# BSPD_TNN_V1_0.net
KiCad netlist of a schematic drawn in EAGLE
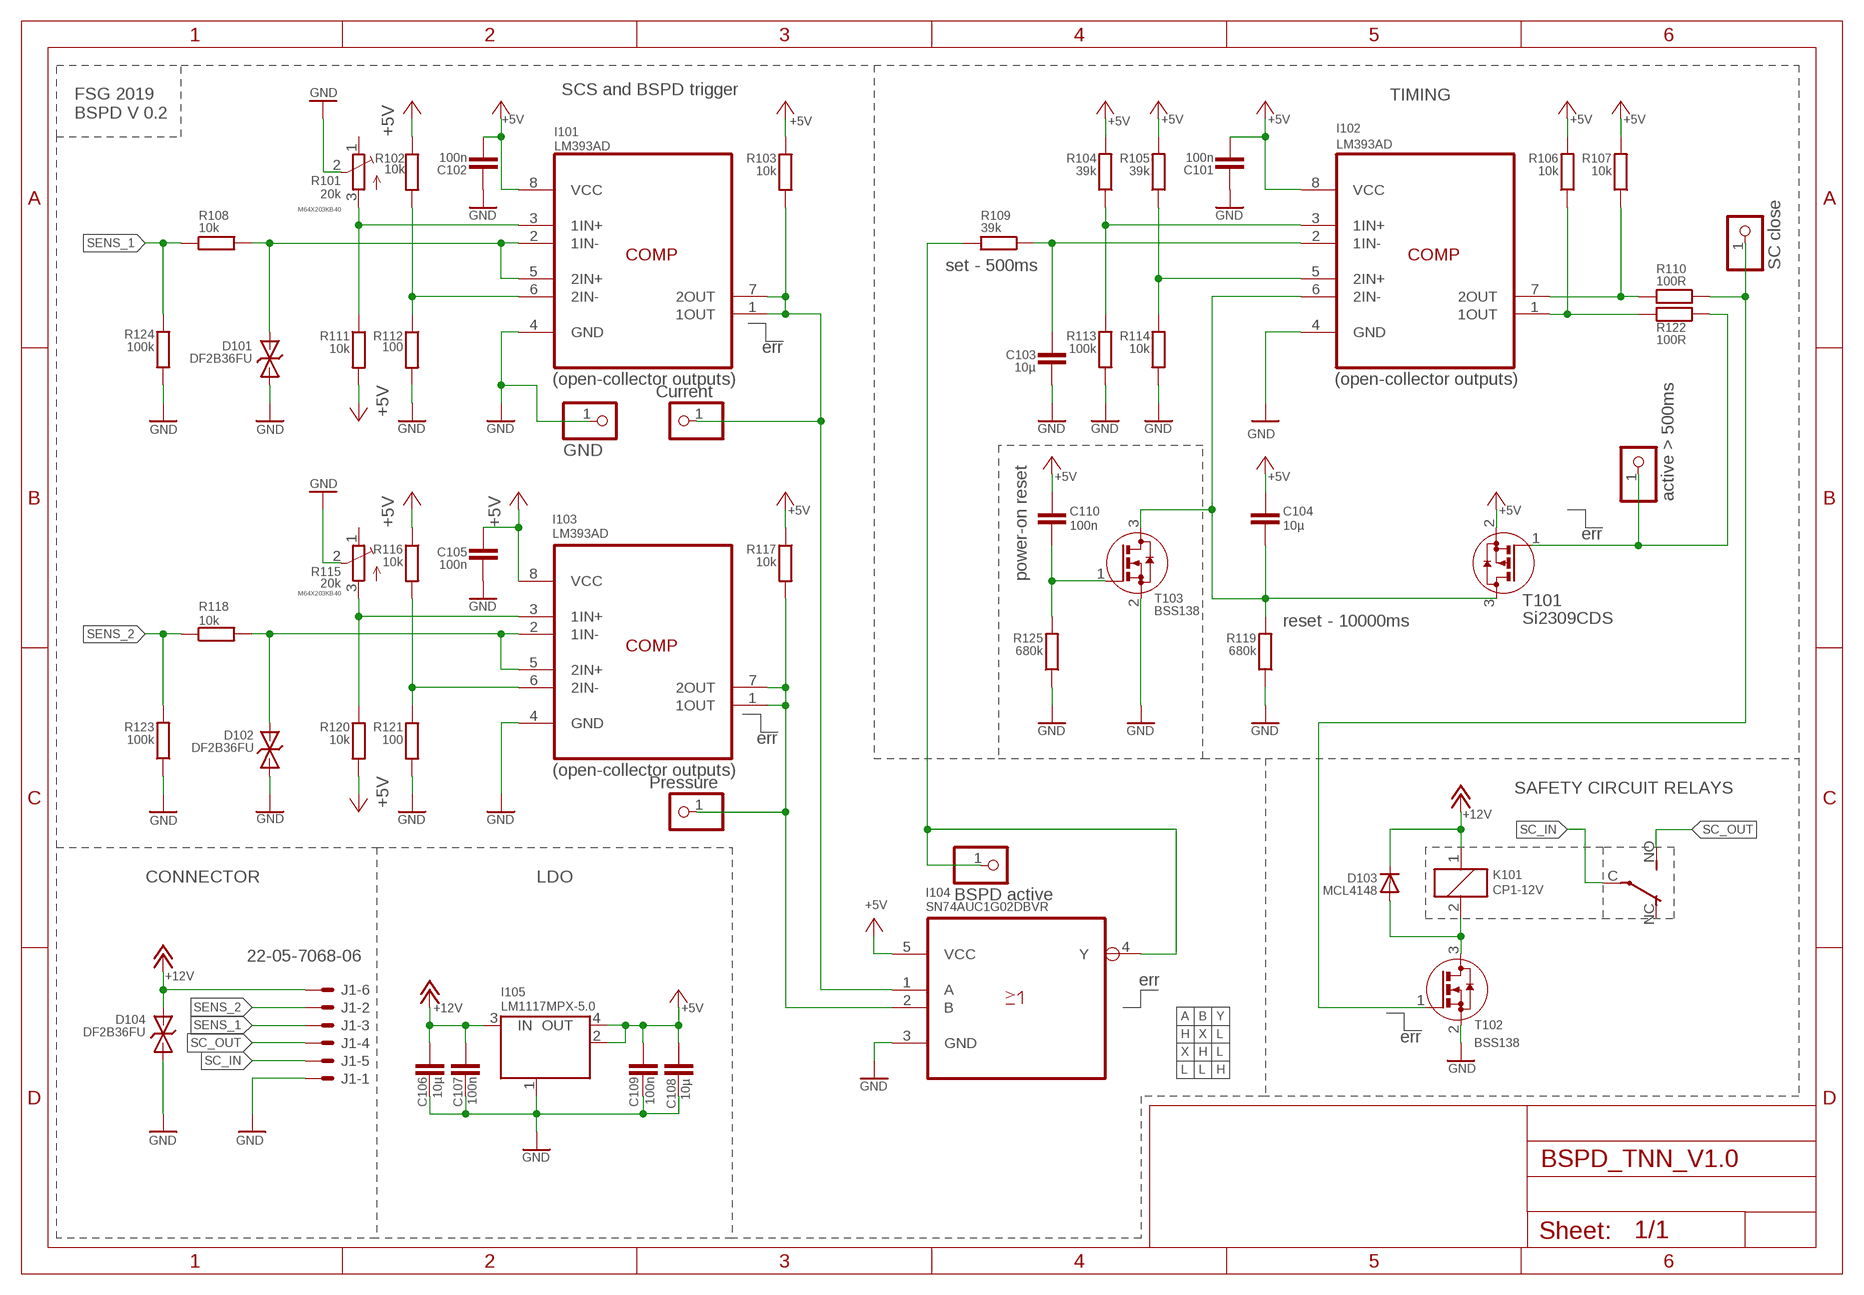
[diagram p0: schematic, sheet 1]

(export (version "E")
  (design (tool "Eeschema 10.0.6"))
  (components
    (comp (ref "C101")
      (value "100n")
      (footprint "eagle-import:C0603")
      (libsource (lib "eagle-import") (part "resistor_C-EUC0603"))
    )
    (comp (ref "C102")
      (value "100n")
      (footprint "eagle-import:C0603")
      (libsource (lib "eagle-import") (part "resistor_C-EUC0603"))
    )
    (comp (ref "C103")
      (value "10µ")
      (footprint "eagle-import:C1206")
      (libsource (lib "eagle-import") (part "C-EUC1206"))
    )
    (comp (ref "C104")
      (value "10µ")
      (footprint "eagle-import:C1206K")
      (libsource (lib "eagle-import") (part "C-EUC1206K"))
    )
    (comp (ref "C105")
      (value "100n")
      (footprint "eagle-import:C0603")
      (libsource (lib "eagle-import") (part "resistor_C-EUC0603"))
    )
    (comp (ref "C106")
      (value "10µ")
      (footprint "eagle-import:C1206")
      (libsource (lib "eagle-import") (part "C-EUC1206"))
    )
    (comp (ref "C107")
      (value "100n")
      (footprint "eagle-import:C0603")
      (libsource (lib "eagle-import") (part "C-EUC0603"))
    )
    (comp (ref "C108")
      (value "10µ")
      (footprint "eagle-import:C1206")
      (libsource (lib "eagle-import") (part "C-EUC1206"))
    )
    (comp (ref "C109")
      (value "100n")
      (footprint "eagle-import:C0603")
      (libsource (lib "eagle-import") (part "C-EUC0603"))
    )
    (comp (ref "C110")
      (value "100n")
      (footprint "eagle-import:C0603")
      (libsource (lib "eagle-import") (part "C-EUC0603"))
    )
    (comp (ref "D101")
      (value "DF2B36FU")
      (footprint "eagle-import:SOD323")
      (libsource (lib "eagle-import") (part "DF2B36FU"))
    )
    (comp (ref "D102")
      (value "DF2B36FU")
      (footprint "eagle-import:SOD323")
      (libsource (lib "eagle-import") (part "DF2B36FU"))
    )
    (comp (ref "D103")
      (value "MCL4148")
      (footprint "eagle-import:MICROMELF")
      (libsource (lib "eagle-import") (part "D.MCL4148"))
    )
    (comp (ref "D104")
      (value "DF2B36FU")
      (footprint "eagle-import:SOD323")
      (libsource (lib "eagle-import") (part "DF2B36FU"))
    )
    (comp (ref "I101")
      (value "LM393AD")
      (footprint "eagle-import:SOIC127P600X175-8N")
      (libsource (lib "eagle-import") (part "LM393AD"))
    )
    (comp (ref "I102")
      (value "LM393AD")
      (footprint "eagle-import:SOIC127P600X175-8N")
      (libsource (lib "eagle-import") (part "LM393AD"))
    )
    (comp (ref "I103")
      (value "LM393AD")
      (footprint "eagle-import:SOIC127P600X175-8N")
      (libsource (lib "eagle-import") (part "LM393AD"))
    )
    (comp (ref "I104")
      (value "SN74AUC1G02DBVR")
      (footprint "eagle-import:SOT95P280X145-5N")
      (fields (field (name "MPN") "NC7SZ08M5X"))
      (libsource (lib "eagle-import") (part "NC7SZ08M5X"))
    )
    (comp (ref "I105")
      (value "LM1117MPX-5.0")
      (footprint "eagle-import:LINEAR_SOT223")
      (fields (field (name "PART_NUMBER") "LM1117IMPX-5.0"))
      (libsource (lib "eagle-import") (part "0022_LM1117IMPX-5.0"))
    )
    (comp (ref "J1")
      (value "22-05-7068-06")
      (footprint "eagle-import:7395-06")
      (fields (field (name "MF") "MOLEX"))
      (libsource (lib "eagle-import") (part "22-?-0605-7068"))
    )
    (comp (ref "JP1")
      (value "Pressure")
      (footprint "eagle-import:1X01")
      (libsource (lib "eagle-import") (part "PINHD-1X1"))
    )
    (comp (ref "JP2")
      (value "Current")
      (footprint "eagle-import:1X01")
      (libsource (lib "eagle-import") (part "PINHD-1X1"))
    )
    (comp (ref "JP3")
      (value "BSPD active")
      (footprint "eagle-import:1X01")
      (libsource (lib "eagle-import") (part "PINHD-1X1"))
    )
    (comp (ref "JP4")
      (value "active > 500ms")
      (footprint "eagle-import:1X01")
      (libsource (lib "eagle-import") (part "PINHD-1X1"))
    )
    (comp (ref "JP5")
      (value "SC close")
      (footprint "eagle-import:1X01")
      (libsource (lib "eagle-import") (part "PINHD-1X1"))
    )
    (comp (ref "JP6")
      (value "GND")
      (footprint "eagle-import:1X01")
      (libsource (lib "eagle-import") (part "PINHD-1X1"))
    )
    (comp (ref "K101")
      (value "CP1-12V")
      (footprint "eagle-import:CP1")
      (fields (field (name "MF") "AROMAT/ MATSUSHITA"))
      (libsource (lib "eagle-import") (part "CP1?-12V"))
    )
    (comp (ref "R101")
      (value "20k")
      (footprint "eagle-import:M64X201KB40")
      (libsource (lib "eagle-import") (part "POTI.M64X201KB40"))
    )
    (comp (ref "R102")
      (value "10k")
      (footprint "eagle-import:R0603")
      (libsource (lib "eagle-import") (part "R-EU_R0603"))
    )
    (comp (ref "R103")
      (value "10k")
      (footprint "eagle-import:R0603")
      (libsource (lib "eagle-import") (part "R-EU_R0603"))
    )
    (comp (ref "R104")
      (value "39k")
      (footprint "eagle-import:R0603")
      (libsource (lib "eagle-import") (part "R-EU_R0603"))
    )
    (comp (ref "R105")
      (value "39k")
      (footprint "eagle-import:R0603")
      (libsource (lib "eagle-import") (part "R-EU_R0603"))
    )
    (comp (ref "R106")
      (value "10k")
      (footprint "eagle-import:R0603")
      (libsource (lib "eagle-import") (part "R-EU_R0603"))
    )
    (comp (ref "R107")
      (value "10k")
      (footprint "eagle-import:R0603")
      (libsource (lib "eagle-import") (part "R-EU_R0603"))
    )
    (comp (ref "R108")
      (value "10k")
      (footprint "eagle-import:R0603")
      (libsource (lib "eagle-import") (part "R-EU_R0603"))
    )
    (comp (ref "R109")
      (value "39k")
      (footprint "eagle-import:R0603")
      (libsource (lib "eagle-import") (part "R-EU_R0603"))
    )
    (comp (ref "R110")
      (value "100R")
      (footprint "eagle-import:R0603")
      (libsource (lib "eagle-import") (part "R-EU_R0603"))
    )
    (comp (ref "R111")
      (value "10k")
      (footprint "eagle-import:R0603")
      (libsource (lib "eagle-import") (part "R-EU_R0603"))
    )
    (comp (ref "R112")
      (value "100")
      (footprint "eagle-import:R0603")
      (libsource (lib "eagle-import") (part "R-EU_R0603"))
    )
    (comp (ref "R113")
      (value "100k")
      (footprint "eagle-import:R0603")
      (libsource (lib "eagle-import") (part "R-EU_R0603"))
    )
    (comp (ref "R114")
      (value "10k")
      (footprint "eagle-import:R0603")
      (libsource (lib "eagle-import") (part "R-EU_R0603"))
    )
    (comp (ref "R115")
      (value "20k")
      (footprint "eagle-import:M64X201KB40")
      (libsource (lib "eagle-import") (part "POTI.M64X201KB40"))
    )
    (comp (ref "R116")
      (value "10k")
      (footprint "eagle-import:R0603")
      (libsource (lib "eagle-import") (part "R-EU_R0603"))
    )
    (comp (ref "R117")
      (value "10k")
      (footprint "eagle-import:R0603")
      (libsource (lib "eagle-import") (part "R-EU_R0603"))
    )
    (comp (ref "R118")
      (value "10k")
      (footprint "eagle-import:R0603")
      (libsource (lib "eagle-import") (part "R-EU_R0603"))
    )
    (comp (ref "R119")
      (value "680k")
      (footprint "eagle-import:R0603")
      (libsource (lib "eagle-import") (part "R-EU_R0603"))
    )
    (comp (ref "R120")
      (value "10k")
      (footprint "eagle-import:R0603")
      (libsource (lib "eagle-import") (part "R-EU_R0603"))
    )
    (comp (ref "R121")
      (value "100")
      (footprint "eagle-import:R0603")
      (libsource (lib "eagle-import") (part "R-EU_R0603"))
    )
    (comp (ref "R122")
      (value "100R")
      (footprint "eagle-import:R0603")
      (libsource (lib "eagle-import") (part "R-EU_R0603"))
    )
    (comp (ref "R123")
      (value "100k")
      (footprint "eagle-import:R0603")
      (libsource (lib "eagle-import") (part "R-EU_R0603"))
    )
    (comp (ref "R124")
      (value "100k")
      (footprint "eagle-import:R0603")
      (libsource (lib "eagle-import") (part "R-EU_R0603"))
    )
    (comp (ref "R125")
      (value "680k")
      (footprint "eagle-import:R0603")
      (libsource (lib "eagle-import") (part "R-EU_R0603"))
    )
    (comp (ref "T101")
      (value "Si2309CDS")
      (footprint "eagle-import:SOT-23")
      (libsource (lib "eagle-import") (part "P-MOSFET.SOT23"))
    )
    (comp (ref "T102")
      (value "BSS138")
      (footprint "eagle-import:SOT-23")
      (libsource (lib "eagle-import") (part "N-MOSFET.SOT23"))
    )
    (comp (ref "T103")
      (value "BSS138")
      (footprint "eagle-import:SOT-23")
      (libsource (lib "eagle-import") (part "N-MOSFET.SOT23"))
    )
  )
  (nets
    (net (code "1") (name "+5V") (class "Default")
      (node (ref "C101") (pin "2") (pinfunction "2_2") (pintype "passive"))
      (node (ref "C102") (pin "2") (pinfunction "2_2") (pintype "passive"))
      (node (ref "C104") (pin "1") (pinfunction "1_1") (pintype "passive"))
      (node (ref "C105") (pin "2") (pinfunction "2_2") (pintype "passive"))
      (node (ref "C108") (pin "1") (pinfunction "1_1") (pintype "passive"))
      (node (ref "C109") (pin "2") (pinfunction "2_2") (pintype "passive"))
      (node (ref "C110") (pin "1") (pinfunction "1_1") (pintype "passive"))
      (node (ref "I101") (pin "8") (pinfunction "VCC_8") (pintype "power_in"))
      (node (ref "I102") (pin "8") (pinfunction "VCC_8") (pintype "power_in"))
      (node (ref "I103") (pin "8") (pinfunction "VCC_8") (pintype "power_in"))
      (node (ref "I104") (pin "5") (pinfunction "VCC_5") (pintype "power_in"))
      (node (ref "I105") (pin "2") (pinfunction "OUT_2") (pintype "passive"))
      (node (ref "I105") (pin "4") (pinfunction "OUT_4") (pintype "passive"))
      (node (ref "R102") (pin "1") (pinfunction "1_1") (pintype "passive"))
      (node (ref "R103") (pin "1") (pinfunction "1_1") (pintype "passive"))
      (node (ref "R104") (pin "2") (pinfunction "2_2") (pintype "passive"))
      (node (ref "R105") (pin "2") (pinfunction "2_2") (pintype "passive"))
      (node (ref "R106") (pin "2") (pinfunction "2_2") (pintype "passive"))
      (node (ref "R107") (pin "2") (pinfunction "2_2") (pintype "passive"))
      (node (ref "R111") (pin "2") (pinfunction "2_2") (pintype "passive"))
      (node (ref "R116") (pin "1") (pinfunction "1_1") (pintype "passive"))
      (node (ref "R117") (pin "1") (pinfunction "1_1") (pintype "passive"))
      (node (ref "R120") (pin "2") (pinfunction "2_2") (pintype "passive"))
      (node (ref "T101") (pin "2") (pinfunction "S_2") (pintype "passive"))
    )
    (net (code "2") (name "+12V") (class "Default")
      (node (ref "C106") (pin "1") (pinfunction "1_1") (pintype "passive"))
      (node (ref "C107") (pin "1") (pinfunction "1_1") (pintype "passive"))
      (node (ref "D103") (pin "C") (pinfunction "C_C") (pintype "passive"))
      (node (ref "D104") (pin "2") (pinfunction "C_2") (pintype "passive"))
      (node (ref "I105") (pin "3") (pinfunction "IN_3") (pintype "input"))
      (node (ref "J1") (pin "6") (pinfunction "S_6") (pintype "passive"))
      (node (ref "K101") (pin "1") (pinfunction "1_1") (pintype "passive"))
    )
    (net (code "3") (name "GND") (class "Default")
      (node (ref "C101") (pin "1") (pinfunction "1_1") (pintype "passive"))
      (node (ref "C102") (pin "1") (pinfunction "1_1") (pintype "passive"))
      (node (ref "C103") (pin "2") (pinfunction "2_2") (pintype "passive"))
      (node (ref "C105") (pin "1") (pinfunction "1_1") (pintype "passive"))
      (node (ref "C106") (pin "2") (pinfunction "2_2") (pintype "passive"))
      (node (ref "C107") (pin "2") (pinfunction "2_2") (pintype "passive"))
      (node (ref "C108") (pin "2") (pinfunction "2_2") (pintype "passive"))
      (node (ref "C109") (pin "1") (pinfunction "1_1") (pintype "passive"))
      (node (ref "D101") (pin "1") (pinfunction "A_1") (pintype "passive"))
      (node (ref "D102") (pin "1") (pinfunction "A_1") (pintype "passive"))
      (node (ref "D104") (pin "1") (pinfunction "A_1") (pintype "passive"))
      (node (ref "I101") (pin "4") (pinfunction "GND_4") (pintype "passive"))
      (node (ref "I102") (pin "4") (pinfunction "GND_4") (pintype "passive"))
      (node (ref "I103") (pin "4") (pinfunction "GND_4") (pintype "passive"))
      (node (ref "I104") (pin "3") (pinfunction "GND_3") (pintype "passive"))
      (node (ref "I105") (pin "1") (pinfunction "GND/ADJ_1") (pintype "input"))
      (node (ref "J1") (pin "1") (pinfunction "S_1") (pintype "passive"))
      (node (ref "JP6") (pin "1") (pinfunction "1_1") (pintype "passive"))
      (node (ref "R101") (pin "2") (pinfunction "M_2") (pintype "passive"))
      (node (ref "R112") (pin "2") (pinfunction "2_2") (pintype "passive"))
      (node (ref "R113") (pin "1") (pinfunction "1_1") (pintype "passive"))
      (node (ref "R114") (pin "1") (pinfunction "1_1") (pintype "passive"))
      (node (ref "R115") (pin "2") (pinfunction "M_2") (pintype "passive"))
      (node (ref "R119") (pin "1") (pinfunction "1_1") (pintype "passive"))
      (node (ref "R121") (pin "2") (pinfunction "2_2") (pintype "passive"))
      (node (ref "R123") (pin "1") (pinfunction "1_1") (pintype "passive"))
      (node (ref "R124") (pin "1") (pinfunction "1_1") (pintype "passive"))
      (node (ref "R125") (pin "1") (pinfunction "1_1") (pintype "passive"))
      (node (ref "T102") (pin "2") (pinfunction "S_2") (pintype "passive"))
      (node (ref "T103") (pin "2") (pinfunction "S_2") (pintype "passive"))
    )
    (net (code "4") (name "Net-(D101-C)") (class "Default")
      (node (ref "D101") (pin "2") (pinfunction "C_2") (pintype "passive"))
      (node (ref "I101") (pin "2") (pinfunction "1IN-_2") (pintype "input"))
      (node (ref "I101") (pin "5") (pinfunction "2IN+_5") (pintype "input"))
      (node (ref "R108") (pin "2") (pinfunction "2_2") (pintype "passive"))
    )
    (net (code "5") (name "Net-(D102-C)") (class "Default")
      (node (ref "D102") (pin "2") (pinfunction "C_2") (pintype "passive"))
      (node (ref "I103") (pin "2") (pinfunction "1IN-_2") (pintype "input"))
      (node (ref "I103") (pin "5") (pinfunction "2IN+_5") (pintype "input"))
      (node (ref "R118") (pin "2") (pinfunction "2_2") (pintype "passive"))
    )
    (net (code "6") (name "Net-(I101-1IN+)") (class "Default")
      (node (ref "I101") (pin "3") (pinfunction "1IN+_3") (pintype "input"))
      (node (ref "R101") (pin "3") (pinfunction "A_3") (pintype "passive"))
      (node (ref "R111") (pin "1") (pinfunction "1_1") (pintype "passive"))
    )
    (net (code "7") (name "Net-(I101-1OUT)") (class "Default")
      (node (ref "I101") (pin "1") (pinfunction "1OUT_1") (pintype "output"))
      (node (ref "I101") (pin "7") (pinfunction "2OUT_7") (pintype "output"))
      (node (ref "I104") (pin "1") (pinfunction "A_1") (pintype "input"))
      (node (ref "JP2") (pin "1") (pinfunction "1_1") (pintype "passive"))
      (node (ref "R103") (pin "2") (pinfunction "2_2") (pintype "passive"))
    )
    (net (code "8") (name "Net-(I101-2IN-)") (class "Default")
      (node (ref "I101") (pin "6") (pinfunction "2IN-_6") (pintype "input"))
      (node (ref "R102") (pin "2") (pinfunction "2_2") (pintype "passive"))
      (node (ref "R112") (pin "1") (pinfunction "1_1") (pintype "passive"))
    )
    (net (code "9") (name "Net-(I102-1IN+)") (class "Default")
      (node (ref "I102") (pin "3") (pinfunction "1IN+_3") (pintype "input"))
      (node (ref "R104") (pin "1") (pinfunction "1_1") (pintype "passive"))
      (node (ref "R113") (pin "2") (pinfunction "2_2") (pintype "passive"))
    )
    (net (code "10") (name "Net-(I102-1IN-)") (class "Default")
      (node (ref "C103") (pin "1") (pinfunction "1_1") (pintype "passive"))
      (node (ref "I102") (pin "2") (pinfunction "1IN-_2") (pintype "input"))
      (node (ref "R109") (pin "1") (pinfunction "1_1") (pintype "passive"))
    )
    (net (code "11") (name "Net-(I102-1OUT)") (class "Default")
      (node (ref "I102") (pin "1") (pinfunction "1OUT_1") (pintype "output"))
      (node (ref "R106") (pin "1") (pinfunction "1_1") (pintype "passive"))
      (node (ref "R122") (pin "2") (pinfunction "2_2") (pintype "passive"))
    )
    (net (code "12") (name "Net-(I102-2IN+)") (class "Default")
      (node (ref "I102") (pin "5") (pinfunction "2IN+_5") (pintype "input"))
      (node (ref "R105") (pin "1") (pinfunction "1_1") (pintype "passive"))
      (node (ref "R114") (pin "2") (pinfunction "2_2") (pintype "passive"))
    )
    (net (code "13") (name "Net-(I102-2IN-)") (class "Default")
      (node (ref "C104") (pin "2") (pinfunction "2_2") (pintype "passive"))
      (node (ref "I102") (pin "6") (pinfunction "2IN-_6") (pintype "input"))
      (node (ref "R119") (pin "2") (pinfunction "2_2") (pintype "passive"))
      (node (ref "T101") (pin "3") (pinfunction "D_3") (pintype "passive"))
      (node (ref "T103") (pin "3") (pinfunction "D_3") (pintype "passive"))
    )
    (net (code "14") (name "Net-(I102-2OUT)") (class "Default")
      (node (ref "I102") (pin "7") (pinfunction "2OUT_7") (pintype "output"))
      (node (ref "R107") (pin "1") (pinfunction "1_1") (pintype "passive"))
      (node (ref "R110") (pin "2") (pinfunction "2_2") (pintype "passive"))
    )
    (net (code "15") (name "Net-(I103-1IN+)") (class "Default")
      (node (ref "I103") (pin "3") (pinfunction "1IN+_3") (pintype "input"))
      (node (ref "R115") (pin "3") (pinfunction "A_3") (pintype "passive"))
      (node (ref "R120") (pin "1") (pinfunction "1_1") (pintype "passive"))
    )
    (net (code "16") (name "Net-(I103-1OUT)") (class "Default")
      (node (ref "I103") (pin "1") (pinfunction "1OUT_1") (pintype "output"))
      (node (ref "I103") (pin "7") (pinfunction "2OUT_7") (pintype "output"))
      (node (ref "I104") (pin "2") (pinfunction "B_2") (pintype "input"))
      (node (ref "JP1") (pin "1") (pinfunction "1_1") (pintype "passive"))
      (node (ref "R117") (pin "2") (pinfunction "2_2") (pintype "passive"))
    )
    (net (code "17") (name "Net-(I103-2IN-)") (class "Default")
      (node (ref "I103") (pin "6") (pinfunction "2IN-_6") (pintype "input"))
      (node (ref "R116") (pin "2") (pinfunction "2_2") (pintype "passive"))
      (node (ref "R121") (pin "1") (pinfunction "1_1") (pintype "passive"))
    )
    (net (code "18") (name "Net-(I104-Y)") (class "Default")
      (node (ref "I104") (pin "4") (pinfunction "Y_4") (pintype "output"))
      (node (ref "JP3") (pin "1") (pinfunction "1_1") (pintype "passive"))
      (node (ref "R109") (pin "2") (pinfunction "2_2") (pintype "passive"))
    )
    (net (code "19") (name "Net-(T101-G)") (class "Default")
      (node (ref "JP4") (pin "1") (pinfunction "1_1") (pintype "passive"))
      (node (ref "R122") (pin "1") (pinfunction "1_1") (pintype "passive"))
      (node (ref "T101") (pin "1") (pinfunction "G_1") (pintype "passive"))
    )
    (net (code "20") (name "Net-(T102-D)") (class "Default")
      (node (ref "D103") (pin "A") (pinfunction "A_A") (pintype "passive"))
      (node (ref "K101") (pin "2") (pinfunction "2_2") (pintype "passive"))
      (node (ref "T102") (pin "3") (pinfunction "D_3") (pintype "passive"))
    )
    (net (code "21") (name "Net-(T102-G)") (class "Default")
      (node (ref "JP5") (pin "1") (pinfunction "1_1") (pintype "passive"))
      (node (ref "R110") (pin "1") (pinfunction "1_1") (pintype "passive"))
      (node (ref "T102") (pin "1") (pinfunction "G_1") (pintype "passive"))
    )
    (net (code "22") (name "Net-(T103-G)") (class "Default")
      (node (ref "C110") (pin "2") (pinfunction "2_2") (pintype "passive"))
      (node (ref "R125") (pin "2") (pinfunction "2_2") (pintype "passive"))
      (node (ref "T103") (pin "1") (pinfunction "G_1") (pintype "passive"))
    )
    (net (code "23") (name "SC_IN") (class "Default")
      (node (ref "J1") (pin "5") (pinfunction "S_5") (pintype "passive"))
      (node (ref "K101") (pin "C") (pinfunction "P_C") (pintype "passive"))
    )
    (net (code "24") (name "SC_OUT") (class "Default")
      (node (ref "J1") (pin "4") (pinfunction "S_4") (pintype "passive"))
      (node (ref "K101") (pin "NO") (pinfunction "S_NO") (pintype "passive"))
    )
    (net (code "25") (name "SENS_1") (class "Default")
      (node (ref "J1") (pin "3") (pinfunction "S_3") (pintype "passive"))
      (node (ref "R108") (pin "1") (pinfunction "1_1") (pintype "passive"))
      (node (ref "R124") (pin "2") (pinfunction "2_2") (pintype "passive"))
    )
    (net (code "26") (name "SENS_2") (class "Default")
      (node (ref "J1") (pin "2") (pinfunction "S_2") (pintype "passive"))
      (node (ref "R118") (pin "1") (pinfunction "1_1") (pintype "passive"))
      (node (ref "R123") (pin "2") (pinfunction "2_2") (pintype "passive"))
    )
    (net (code "27") (name "unconnected-(K101B-O-PadNC)") (class "Default")
      (node (ref "K101") (pin "NC") (pinfunction "O_NC") (pintype "passive"))
    )
    (net (code "28") (name "unconnected-(R101-E-Pad1)") (class "Default")
      (node (ref "R101") (pin "1") (pinfunction "E_1") (pintype "passive"))
    )
    (net (code "29") (name "unconnected-(R115-E-Pad1)") (class "Default")
      (node (ref "R115") (pin "1") (pinfunction "E_1") (pintype "passive"))
    )
  )
)
